# openSipPuff_rev_A.net
KiCad netlist of a schematic drawn in EAGLE
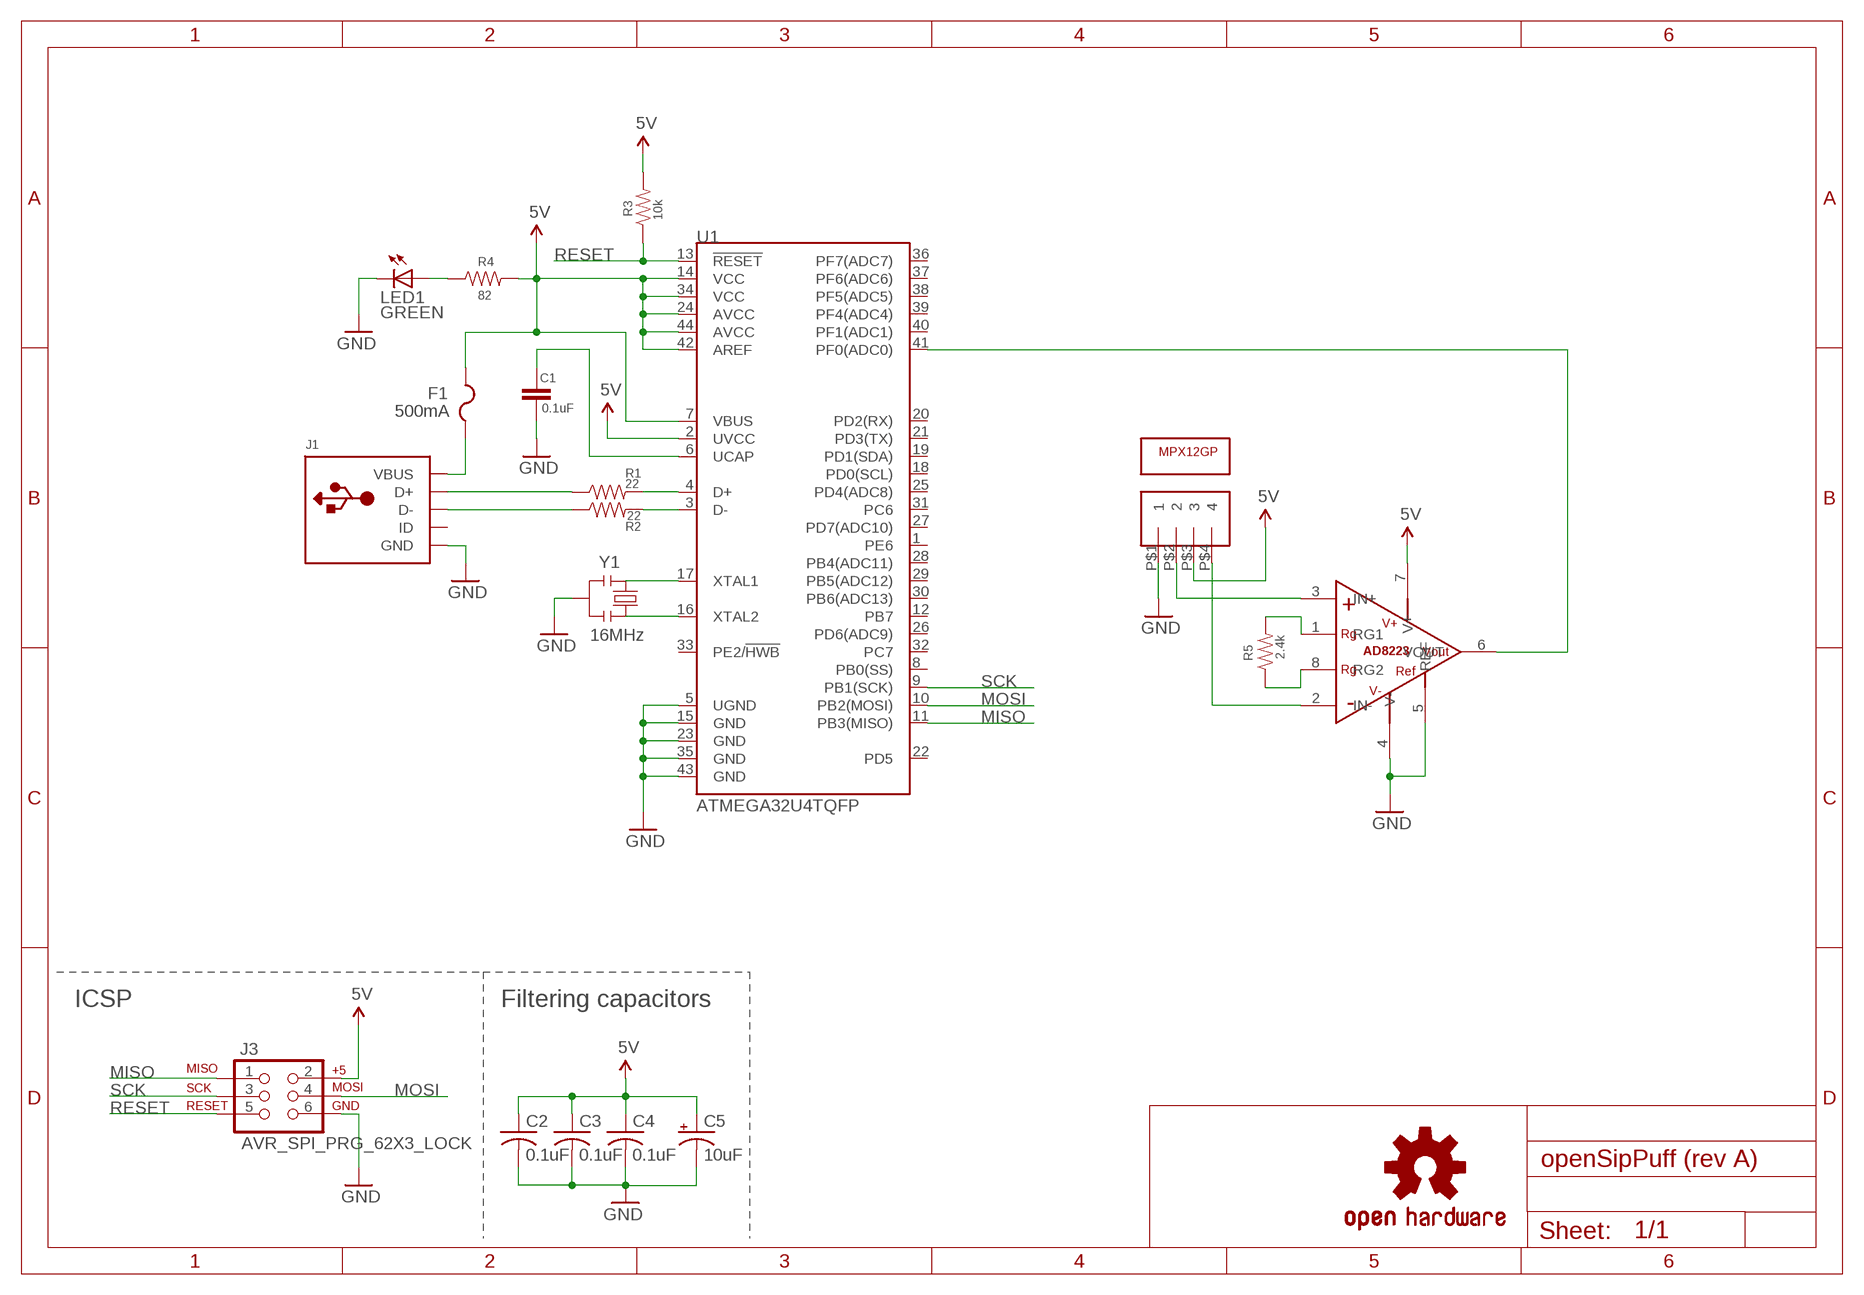
[diagram p0: schematic, sheet 1]

(export (version "E")
  (design (tool "Eeschema 10.0.6"))
  (components
    (comp (ref "C1")
      (value "0.1uF")
      (footprint "eagle-import:0805")
      (libsource (lib "eagle-import") (part "CAP0805"))
    )
    (comp (ref "C2")
      (value "0.1uF")
      (footprint "eagle-import:C0805K")
      (libsource (lib "eagle-import") (part "C-USC0805K"))
    )
    (comp (ref "C3")
      (value "0.1uF")
      (footprint "eagle-import:C0805K")
      (libsource (lib "eagle-import") (part "C-USC0805K"))
    )
    (comp (ref "C4")
      (value "0.1uF")
      (footprint "eagle-import:C0805K")
      (libsource (lib "eagle-import") (part "C-USC0805K"))
    )
    (comp (ref "C5")
      (value "10uF")
      (footprint "eagle-import:A_3216-18R")
      (libsource (lib "eagle-import") (part "CPOL-USA/3216-18R"))
    )
    (comp (ref "F1")
      (value "500mA")
      (footprint "eagle-import:R1206")
      (libsource (lib "eagle-import") (part "PTCFUSE-1206"))
    )
    (comp (ref "J1")
      (value "USBMINIB")
      (footprint "eagle-import:USB-MINIB")
      (libsource (lib "eagle-import") (part "USBMINIB"))
    )
    (comp (ref "J2")
      (value "1X04-RA")
      (footprint "eagle-import:1X04-RA")
      (libsource (lib "eagle-import") (part "1X04-RA"))
    )
    (comp (ref "J3")
      (value "AVR_SPI_PRG_62X3_LOCK")
      (footprint "eagle-import:2X3_LOCK")
      (libsource (lib "eagle-import") (part "AVR_SPI_PRG_62X3_LOCK"))
    )
    (comp (ref "LED1")
      (value "GREEN")
      (footprint "eagle-import:CHIPLED_0805")
      (libsource (lib "eagle-import") (part "LEDCHIPLED_0805"))
    )
    (comp (ref "LOGO1")
      (value "OSHW-LOGOL")
      (footprint "eagle-import:OSHW-LOGO-L")
      (libsource (lib "eagle-import") (part "OSHW-LOGOL"))
    )
    (comp (ref "R1")
      (value "22")
      (footprint "eagle-import:0805")
      (libsource (lib "eagle-import") (part "RESISTOR0805-RES"))
    )
    (comp (ref "R2")
      (value "22")
      (footprint "eagle-import:0805")
      (libsource (lib "eagle-import") (part "RESISTOR0805-RES"))
    )
    (comp (ref "R3")
      (value "10k")
      (footprint "eagle-import:0805")
      (libsource (lib "eagle-import") (part "RESISTOR0805-RES"))
    )
    (comp (ref "R4")
      (value "82")
      (footprint "eagle-import:0805")
      (libsource (lib "eagle-import") (part "RESISTOR0805-RES"))
    )
    (comp (ref "R5")
      (value "2.4k")
      (footprint "eagle-import:0805")
      (libsource (lib "eagle-import") (part "RESISTOR0805-RES"))
    )
    (comp (ref "U1")
      (value "ATMEGA32U4TQFP")
      (footprint "eagle-import:SPARKFUN-DIGITALIC_TQFP44")
      (libsource (lib "eagle-import") (part "ATMEGA32U4TQFP"))
    )
    (comp (ref "U2")
      (value "AD8223")
      (footprint "eagle-import:MSOP-8")
      (libsource (lib "eagle-import") (part "AD8223"))
    )
    (comp (ref "U3")
      (value "MPX12GP")
      (footprint "eagle-import:MPX12GP")
      (libsource (lib "eagle-import") (part "MPX12GP"))
    )
    (comp (ref "Y1")
      (value "16MHz")
      (footprint "eagle-import:RESONATOR-PTH")
      (libsource (lib "eagle-import") (part "RESONATORPTH"))
    )
  )
  (nets
    (net (code "1") (name "/MISO") (class "Default")
      (node (ref "J3") (pin "1") (pinfunction "1_1") (pintype "passive"))
      (node (ref "U1") (pin "11") (pinfunction "PB3(MISO)_11") (pintype "bidirectional"))
    )
    (net (code "2") (name "/MOSI") (class "Default")
      (node (ref "J3") (pin "4") (pinfunction "4_4") (pintype "passive"))
      (node (ref "U1") (pin "10") (pinfunction "PB2(MOSI)_10") (pintype "bidirectional"))
    )
    (net (code "3") (name "/RESET") (class "Default")
      (node (ref "J3") (pin "5") (pinfunction "5_5") (pintype "passive"))
      (node (ref "R3") (pin "1") (pinfunction "1_1") (pintype "passive"))
      (node (ref "U1") (pin "13") (pinfunction "~{RESET}_13") (pintype "bidirectional"))
    )
    (net (code "4") (name "/SCK") (class "Default")
      (node (ref "J3") (pin "3") (pinfunction "3_3") (pintype "passive"))
      (node (ref "U1") (pin "9") (pinfunction "PB1(SCK)_9") (pintype "bidirectional"))
    )
    (net (code "5") (name "5V") (class "Default")
      (node (ref "C2") (pin "1") (pinfunction "1_1") (pintype "passive"))
      (node (ref "C3") (pin "1") (pinfunction "1_1") (pintype "passive"))
      (node (ref "C4") (pin "1") (pinfunction "1_1") (pintype "passive"))
      (node (ref "C5") (pin "+") (pinfunction "+_+") (pintype "passive"))
      (node (ref "F1") (pin "2") (pinfunction "2_2") (pintype "passive"))
      (node (ref "J2") (pin "P$3") (pinfunction "3_P$3") (pintype "power_in"))
      (node (ref "J3") (pin "2") (pinfunction "2_2") (pintype "passive"))
      (node (ref "R3") (pin "2") (pinfunction "2_2") (pintype "passive"))
      (node (ref "R4") (pin "2") (pinfunction "2_2") (pintype "passive"))
      (node (ref "U1") (pin "14") (pinfunction "VCC_14") (pintype "bidirectional"))
      (node (ref "U1") (pin "2") (pinfunction "UVCC_2") (pintype "bidirectional"))
      (node (ref "U1") (pin "24") (pinfunction "AVCC_24") (pintype "bidirectional"))
      (node (ref "U1") (pin "34") (pinfunction "VCC_34") (pintype "bidirectional"))
      (node (ref "U1") (pin "42") (pinfunction "AREF_42") (pintype "bidirectional"))
      (node (ref "U1") (pin "44") (pinfunction "AVCC_44") (pintype "bidirectional"))
      (node (ref "U1") (pin "7") (pinfunction "VBUS_7") (pintype "bidirectional"))
      (node (ref "U2") (pin "7") (pinfunction "V+_7") (pintype "power_in"))
    )
    (net (code "6") (name "GND") (class "Default")
      (node (ref "C1") (pin "2") (pinfunction "2_2") (pintype "passive"))
      (node (ref "C2") (pin "2") (pinfunction "2_2") (pintype "passive"))
      (node (ref "C3") (pin "2") (pinfunction "2_2") (pintype "passive"))
      (node (ref "C4") (pin "2") (pinfunction "2_2") (pintype "passive"))
      (node (ref "C5") (pin "-") (pinfunction "-_-") (pintype "passive"))
      (node (ref "J1") (pin "GND") (pinfunction "GND_GND") (pintype "power_in"))
      (node (ref "J2") (pin "P$1") (pinfunction "1_P$1") (pintype "power_in"))
      (node (ref "J3") (pin "6") (pinfunction "6_6") (pintype "passive"))
      (node (ref "LED1") (pin "C") (pinfunction "C_C") (pintype "passive"))
      (node (ref "U1") (pin "15") (pinfunction "GND_15") (pintype "bidirectional"))
      (node (ref "U1") (pin "23") (pinfunction "GND_23") (pintype "bidirectional"))
      (node (ref "U1") (pin "35") (pinfunction "GND_35") (pintype "bidirectional"))
      (node (ref "U1") (pin "43") (pinfunction "GND_43") (pintype "bidirectional"))
      (node (ref "U1") (pin "5") (pinfunction "UGND_5") (pintype "bidirectional"))
      (node (ref "U2") (pin "4") (pinfunction "V-_4") (pintype "power_in"))
      (node (ref "U2") (pin "5") (pinfunction "REF_5") (pintype "bidirectional"))
      (node (ref "Y1") (pin "2") (pinfunction "2_2") (pintype "passive"))
    )
    (net (code "7") (name "Net-(F1-Pad1)") (class "Default")
      (node (ref "F1") (pin "1") (pinfunction "1_1") (pintype "passive"))
      (node (ref "J1") (pin "VBUS") (pinfunction "VBUS_VBUS") (pintype "power_in"))
    )
    (net (code "8") (name "Net-(J1-PadD+)") (class "Default")
      (node (ref "J1") (pin "D+") (pinfunction "D+_D+") (pintype "bidirectional"))
      (node (ref "R1") (pin "1") (pinfunction "1_1") (pintype "passive"))
    )
    (net (code "9") (name "Net-(J1-PadD-)") (class "Default")
      (node (ref "J1") (pin "D-") (pinfunction "D-_D-") (pintype "bidirectional"))
      (node (ref "R2") (pin "1") (pinfunction "1_1") (pintype "passive"))
    )
    (net (code "10") (name "Net-(J2-2)") (class "Default")
      (node (ref "J2") (pin "P$2") (pinfunction "2_P$2") (pintype "output"))
      (node (ref "U2") (pin "3") (pinfunction "IN+_3") (pintype "input"))
    )
    (net (code "11") (name "Net-(J2-4)") (class "Default")
      (node (ref "J2") (pin "P$4") (pinfunction "4_P$4") (pintype "output"))
      (node (ref "U2") (pin "2") (pinfunction "IN-_2") (pintype "input"))
    )
    (net (code "12") (name "Net-(LED1-PadA)") (class "Default")
      (node (ref "LED1") (pin "A") (pinfunction "A_A") (pintype "passive"))
      (node (ref "R4") (pin "1") (pinfunction "1_1") (pintype "passive"))
    )
    (net (code "13") (name "Net-(U1-D+)") (class "Default")
      (node (ref "R1") (pin "2") (pinfunction "2_2") (pintype "passive"))
      (node (ref "U1") (pin "4") (pinfunction "D+_4") (pintype "bidirectional"))
    )
    (net (code "14") (name "Net-(U1-D-)") (class "Default")
      (node (ref "R2") (pin "2") (pinfunction "2_2") (pintype "passive"))
      (node (ref "U1") (pin "3") (pinfunction "D-_3") (pintype "bidirectional"))
    )
    (net (code "15") (name "Net-(U1-PF0(ADC0))") (class "Default")
      (node (ref "U1") (pin "41") (pinfunction "PF0(ADC0)_41") (pintype "bidirectional"))
      (node (ref "U2") (pin "6") (pinfunction "VOUT_6") (pintype "output"))
    )
    (net (code "16") (name "Net-(U1-UCAP)") (class "Default")
      (node (ref "C1") (pin "1") (pinfunction "1_1") (pintype "passive"))
      (node (ref "U1") (pin "6") (pinfunction "UCAP_6") (pintype "bidirectional"))
    )
    (net (code "17") (name "Net-(U1-XTAL1)") (class "Default")
      (node (ref "U1") (pin "17") (pinfunction "XTAL1_17") (pintype "bidirectional"))
      (node (ref "Y1") (pin "1") (pinfunction "1_1") (pintype "passive"))
    )
    (net (code "18") (name "Net-(U1-XTAL2)") (class "Default")
      (node (ref "U1") (pin "16") (pinfunction "XTAL2_16") (pintype "bidirectional"))
      (node (ref "Y1") (pin "3") (pinfunction "3_3") (pintype "passive"))
    )
    (net (code "19") (name "Net-(U2-RG1)") (class "Default")
      (node (ref "R5") (pin "2") (pinfunction "2_2") (pintype "passive"))
      (node (ref "U2") (pin "1") (pinfunction "RG1_1") (pintype "input"))
    )
    (net (code "20") (name "Net-(U2-RG2)") (class "Default")
      (node (ref "R5") (pin "1") (pinfunction "1_1") (pintype "passive"))
      (node (ref "U2") (pin "8") (pinfunction "RG2_8") (pintype "input"))
    )
    (net (code "21") (name "unconnected-(J1-PadID)") (class "Default")
      (node (ref "J1") (pin "ID") (pinfunction "ID_ID") (pintype "bidirectional"))
    )
    (net (code "22") (name "unconnected-(U1-PB0(SS)-Pad8)") (class "Default")
      (node (ref "U1") (pin "8") (pinfunction "PB0(SS)_8") (pintype "bidirectional"))
    )
    (net (code "23") (name "unconnected-(U1-PB4(ADC11)-Pad28)") (class "Default")
      (node (ref "U1") (pin "28") (pinfunction "PB4(ADC11)_28") (pintype "bidirectional"))
    )
    (net (code "24") (name "unconnected-(U1-PB5(ADC12)-Pad29)") (class "Default")
      (node (ref "U1") (pin "29") (pinfunction "PB5(ADC12)_29") (pintype "bidirectional"))
    )
    (net (code "25") (name "unconnected-(U1-PB6(ADC13)-Pad30)") (class "Default")
      (node (ref "U1") (pin "30") (pinfunction "PB6(ADC13)_30") (pintype "bidirectional"))
    )
    (net (code "26") (name "unconnected-(U1-PB7-Pad12)") (class "Default")
      (node (ref "U1") (pin "12") (pinfunction "PB7_12") (pintype "bidirectional"))
    )
    (net (code "27") (name "unconnected-(U1-PC6-Pad31)") (class "Default")
      (node (ref "U1") (pin "31") (pinfunction "PC6_31") (pintype "bidirectional"))
    )
    (net (code "28") (name "unconnected-(U1-PC7-Pad32)") (class "Default")
      (node (ref "U1") (pin "32") (pinfunction "PC7_32") (pintype "bidirectional"))
    )
    (net (code "29") (name "unconnected-(U1-PD0(SCL)-Pad18)") (class "Default")
      (node (ref "U1") (pin "18") (pinfunction "PD0(SCL)_18") (pintype "bidirectional"))
    )
    (net (code "30") (name "unconnected-(U1-PD1(SDA)-Pad19)") (class "Default")
      (node (ref "U1") (pin "19") (pinfunction "PD1(SDA)_19") (pintype "bidirectional"))
    )
    (net (code "31") (name "unconnected-(U1-PD2(RX)-Pad20)") (class "Default")
      (node (ref "U1") (pin "20") (pinfunction "PD2(RX)_20") (pintype "bidirectional"))
    )
    (net (code "32") (name "unconnected-(U1-PD3(TX)-Pad21)") (class "Default")
      (node (ref "U1") (pin "21") (pinfunction "PD3(TX)_21") (pintype "bidirectional"))
    )
    (net (code "33") (name "unconnected-(U1-PD4(ADC8)-Pad25)") (class "Default")
      (node (ref "U1") (pin "25") (pinfunction "PD4(ADC8)_25") (pintype "bidirectional"))
    )
    (net (code "34") (name "unconnected-(U1-PD5-Pad22)") (class "Default")
      (node (ref "U1") (pin "22") (pinfunction "PD5_22") (pintype "bidirectional"))
    )
    (net (code "35") (name "unconnected-(U1-PD6(ADC9)-Pad26)") (class "Default")
      (node (ref "U1") (pin "26") (pinfunction "PD6(ADC9)_26") (pintype "bidirectional"))
    )
    (net (code "36") (name "unconnected-(U1-PD7(ADC10)-Pad27)") (class "Default")
      (node (ref "U1") (pin "27") (pinfunction "PD7(ADC10)_27") (pintype "bidirectional"))
    )
    (net (code "37") (name "unconnected-(U1-PE2{slash}~{HWB}-Pad33)") (class "Default")
      (node (ref "U1") (pin "33") (pinfunction "PE2/~{HWB}_33") (pintype "bidirectional"))
    )
    (net (code "38") (name "unconnected-(U1-PE6-Pad1)") (class "Default")
      (node (ref "U1") (pin "1") (pinfunction "PE6_1") (pintype "bidirectional"))
    )
    (net (code "39") (name "unconnected-(U1-PF1(ADC1)-Pad40)") (class "Default")
      (node (ref "U1") (pin "40") (pinfunction "PF1(ADC1)_40") (pintype "bidirectional"))
    )
    (net (code "40") (name "unconnected-(U1-PF4(ADC4)-Pad39)") (class "Default")
      (node (ref "U1") (pin "39") (pinfunction "PF4(ADC4)_39") (pintype "bidirectional"))
    )
    (net (code "41") (name "unconnected-(U1-PF5(ADC5)-Pad38)") (class "Default")
      (node (ref "U1") (pin "38") (pinfunction "PF5(ADC5)_38") (pintype "bidirectional"))
    )
    (net (code "42") (name "unconnected-(U1-PF6(ADC6)-Pad37)") (class "Default")
      (node (ref "U1") (pin "37") (pinfunction "PF6(ADC6)_37") (pintype "bidirectional"))
    )
    (net (code "43") (name "unconnected-(U1-PF7(ADC7)-Pad36)") (class "Default")
      (node (ref "U1") (pin "36") (pinfunction "PF7(ADC7)_36") (pintype "bidirectional"))
    )
  )
)
